# Analog_Out.net
KiCad netlist of a schematic drawn in Altium Designer
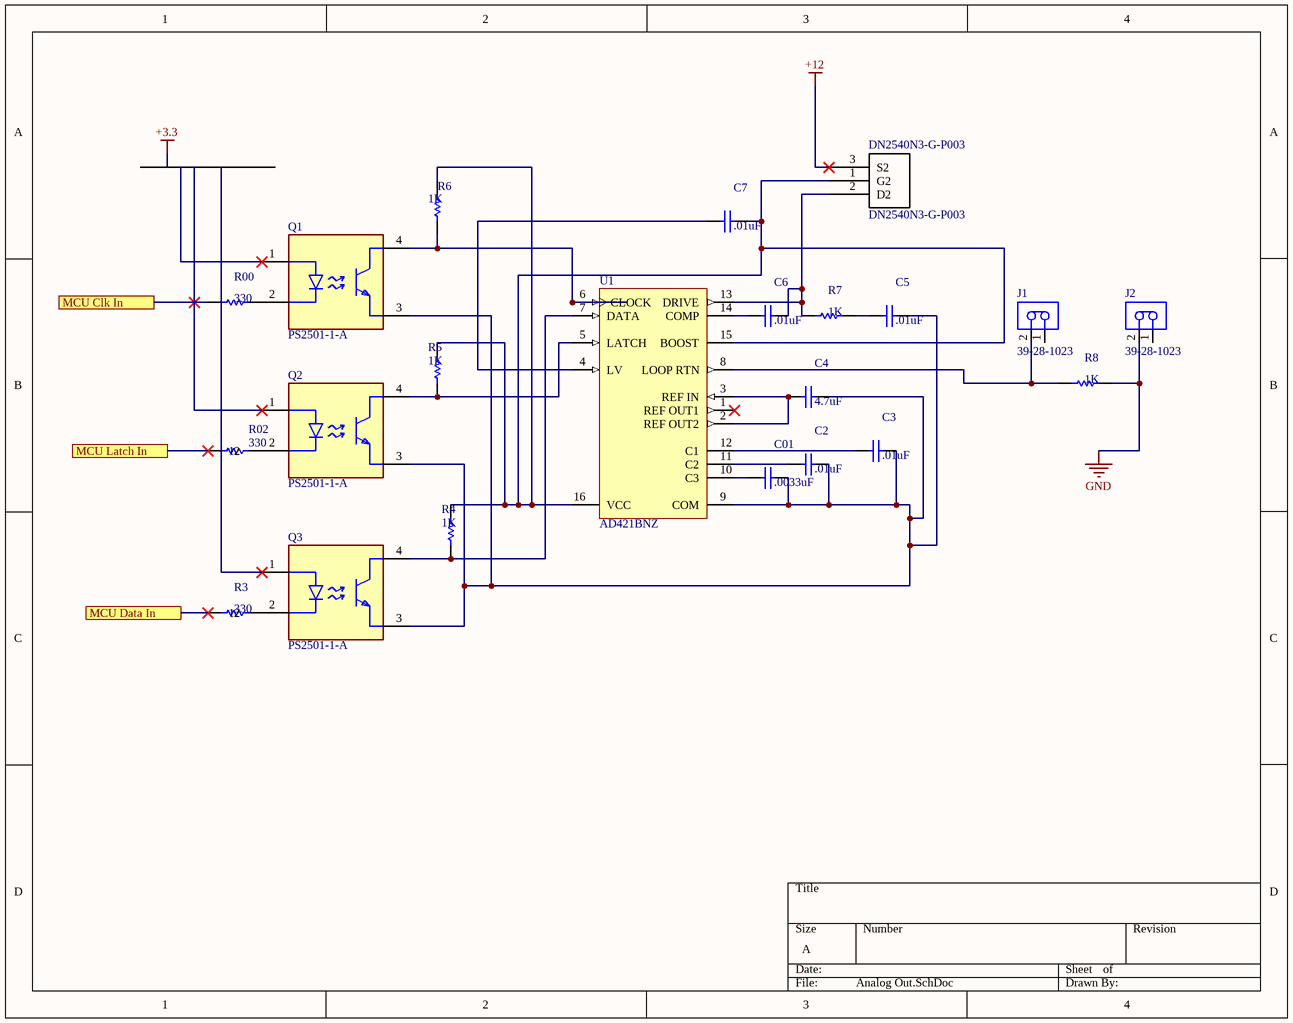
[diagram p0: Analog Out.SchDoc]

(export (version "E")
  (design (tool "Eeschema 10.0.6"))
  (components
    (comp (ref "C01")
      (value ".0033uF")
      (footprint "RAD-0.3")
      (description "Capacitor")
      (fields (field (name "Comment") "Cap") (field (name "PUBLISHER") "Altium Limited"))
      (libsource (lib "Miscellaneous Devices") (part "Cap"))
    )
    (comp (ref "C2")
      (value ".01uF")
      (footprint "RAD-0.3")
      (description "Capacitor")
      (fields (field (name "Comment") "Cap") (field (name "PUBLISHER") "Altium Limited"))
      (libsource (lib "Miscellaneous Devices") (part "Cap"))
    )
    (comp (ref "C3")
      (value ".01uF")
      (footprint "RAD-0.3")
      (description "Capacitor")
      (fields (field (name "Comment") "Cap") (field (name "PUBLISHER") "Altium Limited"))
      (libsource (lib "Miscellaneous Devices") (part "Cap"))
    )
    (comp (ref "C4")
      (value "4.7uF")
      (footprint "RAD-0.3")
      (description "Capacitor")
      (fields (field (name "Comment") "Cap") (field (name "PUBLISHER") "Altium Limited"))
      (libsource (lib "Miscellaneous Devices") (part "Cap"))
    )
    (comp (ref "C5")
      (value ".01uF")
      (footprint "RAD-0.3")
      (description "Capacitor")
      (fields (field (name "Comment") "Cap") (field (name "PUBLISHER") "Altium Limited"))
      (libsource (lib "Miscellaneous Devices") (part "Cap"))
    )
    (comp (ref "C6")
      (value ".01uF")
      (footprint "RAD-0.3")
      (description "Capacitor")
      (fields (field (name "Comment") "Cap") (field (name "PUBLISHER") "Altium Limited"))
      (libsource (lib "Miscellaneous Devices") (part "Cap"))
    )
    (comp (ref "C7")
      (value ".01uF")
      (footprint "RAD-0.3")
      (description "Capacitor")
      (fields (field (name "Comment") "Cap") (field (name "PUBLISHER") "Altium Limited"))
      (libsource (lib "Miscellaneous Devices") (part "Cap"))
    )
    (comp (ref "DN2540N3-G-P003")
      (value "DN2540N3-G-P003")
      (footprint "TO-92")
      (libsource (lib "Parts") (part "DN2540N3-G-P003"))
    )
    (comp (ref "J1")
      (value "39-28-1023")
      (footprint "MOLX-39-28-1023-2_V")
      (fields (field (name "MANUFACTURER") "Molex"))
      (libsource (lib "Board2Wire Components - 02.02.23 - 18.32") (part "CMP-2000-05244-1"))
    )
    (comp (ref "J2")
      (value "39-28-1023")
      (footprint "MOLX-39-28-1023-2_V")
      (fields (field (name "MANUFACTURER") "Molex"))
      (libsource (lib "Board2Wire Components - 02.02.23 - 18.32") (part "CMP-2000-05244-1"))
    )
    (comp (ref "Q1")
      (value "PS2501-1-A")
      (footprint "FP-PS2501-1-A-MFG")
      (description "OPTOISOLATOR 5KV TRANS 4DIP")
      (libsource (lib "Altium Content Vault") (part "9c0182559cfc66618ddd85553301ae2"))
    )
    (comp (ref "Q2")
      (value "PS2501-1-A")
      (footprint "FP-PS2501-1-A-MFG")
      (description "OPTOISOLATOR 5KV TRANS 4DIP")
      (libsource (lib "Altium Content Vault") (part "9c0182559cfc66618ddd85553301ae2"))
    )
    (comp (ref "Q3")
      (value "PS2501-1-A")
      (footprint "FP-PS2501-1-A-MFG")
      (description "OPTOISOLATOR 5KV TRANS 4DIP")
      (libsource (lib "Altium Content Vault") (part "9c0182559cfc66618ddd85553301ae2"))
    )
    (comp (ref "R00")
      (value "330")
      (footprint "AXIAL-0.3")
      (description "Resistor")
      (fields (field (name "Comment") "Res1") (field (name "PUBLISHER") "Altium Limited"))
      (libsource (lib "Miscellaneous Devices") (part "Res1"))
    )
    (comp (ref "R02")
      (value "330")
      (footprint "AXIAL-0.3")
      (description "Resistor")
      (fields (field (name "Comment") "Res1") (field (name "PUBLISHER") "Altium Limited"))
      (libsource (lib "") (part "Res1_1"))
    )
    (comp (ref "R3")
      (value "330")
      (footprint "AXIAL-0.3")
      (description "Resistor")
      (fields (field (name "Comment") "Res1") (field (name "PUBLISHER") "Altium Limited"))
      (libsource (lib "") (part "Res1_1"))
    )
    (comp (ref "R4")
      (value "1K")
      (footprint "AXIAL-0.3")
      (description "Resistor")
      (fields (field (name "Comment") "Res1") (field (name "PUBLISHER") "Altium Limited"))
      (libsource (lib "Miscellaneous Devices") (part "Res1"))
    )
    (comp (ref "R5")
      (value "1K")
      (footprint "AXIAL-0.3")
      (description "Resistor")
      (fields (field (name "Comment") "Res1") (field (name "PUBLISHER") "Altium Limited"))
      (libsource (lib "Miscellaneous Devices") (part "Res1"))
    )
    (comp (ref "R6")
      (value "1K")
      (footprint "AXIAL-0.3")
      (description "Resistor")
      (fields (field (name "Comment") "Res1") (field (name "PUBLISHER") "Altium Limited"))
      (libsource (lib "Miscellaneous Devices") (part "Res1"))
    )
    (comp (ref "R7")
      (value "1K")
      (footprint "AXIAL-0.3")
      (description "Resistor")
      (fields (field (name "Comment") "Res1") (field (name "PUBLISHER") "Altium Limited"))
      (libsource (lib "Miscellaneous Devices") (part "Res1"))
    )
    (comp (ref "R8")
      (value "1K")
      (footprint "AXIAL-0.3")
      (description "Resistor")
      (fields (field (name "Comment") "Res1") (field (name "PUBLISHER") "Altium Limited"))
      (libsource (lib "Miscellaneous Devices") (part "Res1"))
    )
    (comp (ref "U1")
      (value "AD421BNZ")
      (footprint "N-16")
      (fields (field (name "MANUFACTURER") "Analog Devices") (field (name "GENERIC PART NUMBER") "AD421"))
      (libsource (lib "Altium Content Vault") (part "ADI-AD421-N-16"))
    )
  )
  (nets
    (net (code "2") (name "+12") (class "Default")
      (node (ref "DN2540N3-G-P003") (pin "3") (pinfunction "S2_3") (pintype "passive"))
    )
    (net (code "3") (name "/MCU Clk In") (class "Default")
      (node (ref "R00") (pin "1") (pinfunction "1_1") (pintype "passive"))
    )
    (net (code "4") (name "/MCU Data In") (class "Default")
      (node (ref "R3") (pin "1") (pinfunction "1_1") (pintype "passive+no_connect"))
    )
    (net (code "5") (name "/MCU Latch In") (class "Default")
      (node (ref "R02") (pin "1") (pinfunction "1_1") (pintype "passive+no_connect"))
    )
    (net (code "6") (name "GND") (class "Default")
      (node (ref "J2") (pin "2") (pinfunction "2_2") (pintype "passive"))
      (node (ref "R8") (pin "2") (pinfunction "2_2") (pintype "passive"))
    )
    (net (code "7") (name "Net-(C5-Pad1)") (class "Default")
      (node (ref "C5") (pin "1") (pinfunction "1_1") (pintype "passive"))
      (node (ref "R7") (pin "2") (pinfunction "2_2") (pintype "passive"))
    )
    (net (code "8") (name "Net-(DN2540N3-G-P003-D2)") (class "Default")
      (node (ref "C6") (pin "2") (pinfunction "2_2") (pintype "passive"))
      (node (ref "DN2540N3-G-P003") (pin "2") (pinfunction "D2_2") (pintype "passive"))
      (node (ref "R7") (pin "1") (pinfunction "1_1") (pintype "passive"))
      (node (ref "U1") (pin "13") (pinfunction "DRIVE_13") (pintype "output"))
    )
    (net (code "9") (name "Net-(DN2540N3-G-P003-G2)") (class "Default")
      (node (ref "C7") (pin "2") (pinfunction "2_2") (pintype "passive"))
      (node (ref "DN2540N3-G-P003") (pin "1") (pinfunction "G2_1") (pintype "passive"))
      (node (ref "R4") (pin "2") (pinfunction "2_2") (pintype "passive"))
      (node (ref "R5") (pin "2") (pinfunction "2_2") (pintype "passive"))
      (node (ref "R6") (pin "2") (pinfunction "2_2") (pintype "passive"))
      (node (ref "U1") (pin "15") (pinfunction "BOOST_15") (pintype "passive"))
      (node (ref "U1") (pin "16") (pinfunction "VCC_16") (pintype "power_in"))
    )
    (net (code "10") (name "Net-(Q1-C-Pad2)") (class "Default")
      (node (ref "Q1") (pin "2") (pinfunction "C_2") (pintype "passive"))
      (node (ref "R00") (pin "2") (pinfunction "2_2") (pintype "passive"))
    )
    (net (code "11") (name "Net-(Q1-E)") (class "Default")
      (node (ref "C01") (pin "2") (pinfunction "2_2") (pintype "passive"))
      (node (ref "C2") (pin "2") (pinfunction "2_2") (pintype "passive"))
      (node (ref "C3") (pin "2") (pinfunction "2_2") (pintype "passive"))
      (node (ref "C4") (pin "2") (pinfunction "2_2") (pintype "passive"))
      (node (ref "C5") (pin "2") (pinfunction "2_2") (pintype "passive"))
      (node (ref "Q1") (pin "3") (pinfunction "E_3") (pintype "passive"))
      (node (ref "Q2") (pin "3") (pinfunction "E_3") (pintype "passive"))
      (node (ref "Q3") (pin "3") (pinfunction "E_3") (pintype "passive"))
      (node (ref "U1") (pin "9") (pinfunction "COM_9") (pintype "power_in"))
    )
    (net (code "12") (name "Net-(Q2-C-Pad2)") (class "Default")
      (node (ref "Q2") (pin "2") (pinfunction "C_2") (pintype "passive"))
      (node (ref "R02") (pin "2") (pinfunction "2_2") (pintype "passive"))
    )
    (net (code "13") (name "Net-(Q3-C-Pad2)") (class "Default")
      (node (ref "Q3") (pin "2") (pinfunction "C_2") (pintype "passive"))
      (node (ref "R3") (pin "2") (pinfunction "2_2") (pintype "passive"))
    )
    (net (code "14") (name "Net-(U1-C1)") (class "Default")
      (node (ref "C3") (pin "1") (pinfunction "1_1") (pintype "passive"))
      (node (ref "U1") (pin "12") (pinfunction "C1_12") (pintype "passive"))
    )
    (net (code "15") (name "Net-(U1-C2)") (class "Default")
      (node (ref "C2") (pin "1") (pinfunction "1_1") (pintype "passive"))
      (node (ref "U1") (pin "11") (pinfunction "C2_11") (pintype "passive"))
    )
    (net (code "16") (name "Net-(U1-C3)") (class "Default")
      (node (ref "C01") (pin "1") (pinfunction "1_1") (pintype "passive"))
      (node (ref "U1") (pin "10") (pinfunction "C3_10") (pintype "passive"))
    )
    (net (code "17") (name "Net-(U1-CLOCK)") (class "Default")
      (node (ref "Q1") (pin "4") (pinfunction "C_4") (pintype "passive"))
      (node (ref "R6") (pin "1") (pinfunction "1_1") (pintype "passive"))
      (node (ref "U1") (pin "6") (pinfunction "CLOCK_6") (pintype "input"))
    )
    (net (code "18") (name "Net-(U1-COMP)") (class "Default")
      (node (ref "C6") (pin "1") (pinfunction "1_1") (pintype "passive"))
      (node (ref "U1") (pin "14") (pinfunction "COMP_14") (pintype "passive"))
    )
    (net (code "19") (name "Net-(U1-DATA)") (class "Default")
      (node (ref "Q3") (pin "4") (pinfunction "C_4") (pintype "passive"))
      (node (ref "R4") (pin "1") (pinfunction "1_1") (pintype "passive"))
      (node (ref "U1") (pin "7") (pinfunction "DATA_7") (pintype "input"))
    )
    (net (code "20") (name "Net-(U1-LATCH)") (class "Default")
      (node (ref "Q2") (pin "4") (pinfunction "C_4") (pintype "passive"))
      (node (ref "R5") (pin "1") (pinfunction "1_1") (pintype "passive"))
      (node (ref "U1") (pin "5") (pinfunction "LATCH_5") (pintype "input"))
    )
    (net (code "21") (name "Net-(U1-LOOP_RTN)") (class "Default")
      (node (ref "J1") (pin "2") (pinfunction "2_2") (pintype "passive"))
      (node (ref "R8") (pin "1") (pinfunction "1_1") (pintype "passive"))
      (node (ref "U1") (pin "8") (pinfunction "LOOP_RTN_8") (pintype "output"))
    )
    (net (code "22") (name "Net-(U1-LV)") (class "Default")
      (node (ref "C7") (pin "1") (pinfunction "1_1") (pintype "passive"))
      (node (ref "U1") (pin "4") (pinfunction "LV_4") (pintype "input"))
    )
    (net (code "23") (name "Net-(U1-REF_IN)") (class "Default")
      (node (ref "C4") (pin "1") (pinfunction "1_1") (pintype "passive"))
      (node (ref "U1") (pin "2") (pinfunction "REF_OUT2_2") (pintype "output"))
      (node (ref "U1") (pin "3") (pinfunction "REF_IN_3") (pintype "input"))
    )
    (net (code "24") (name "unconnected-(J1-Pad1)") (class "Default")
      (node (ref "J1") (pin "1") (pinfunction "1_1") (pintype "passive"))
    )
    (net (code "25") (name "unconnected-(J2-Pad1)") (class "Default")
      (node (ref "J2") (pin "1") (pinfunction "1_1") (pintype "passive"))
    )
    (net (code "26") (name "unconnected-(Q1-A-Pad1)") (class "Default")
      (node (ref "Q1") (pin "1") (pinfunction "A_1") (pintype "passive+no_connect"))
    )
    (net (code "27") (name "unconnected-(Q2-A-Pad1)") (class "Default")
      (node (ref "Q2") (pin "1") (pinfunction "A_1") (pintype "passive+no_connect"))
    )
    (net (code "28") (name "unconnected-(Q3-A-Pad1)") (class "Default")
      (node (ref "Q3") (pin "1") (pinfunction "A_1") (pintype "passive+no_connect"))
    )
    (net (code "29") (name "unconnected-(U1-REF_OUT1-Pad1)") (class "Default")
      (node (ref "U1") (pin "1") (pinfunction "REF_OUT1_1") (pintype "output+no_connect"))
    )
  )
)
